# 1_Power_and_sensors.net
KiCad netlist of a schematic drawn in Altium Designer
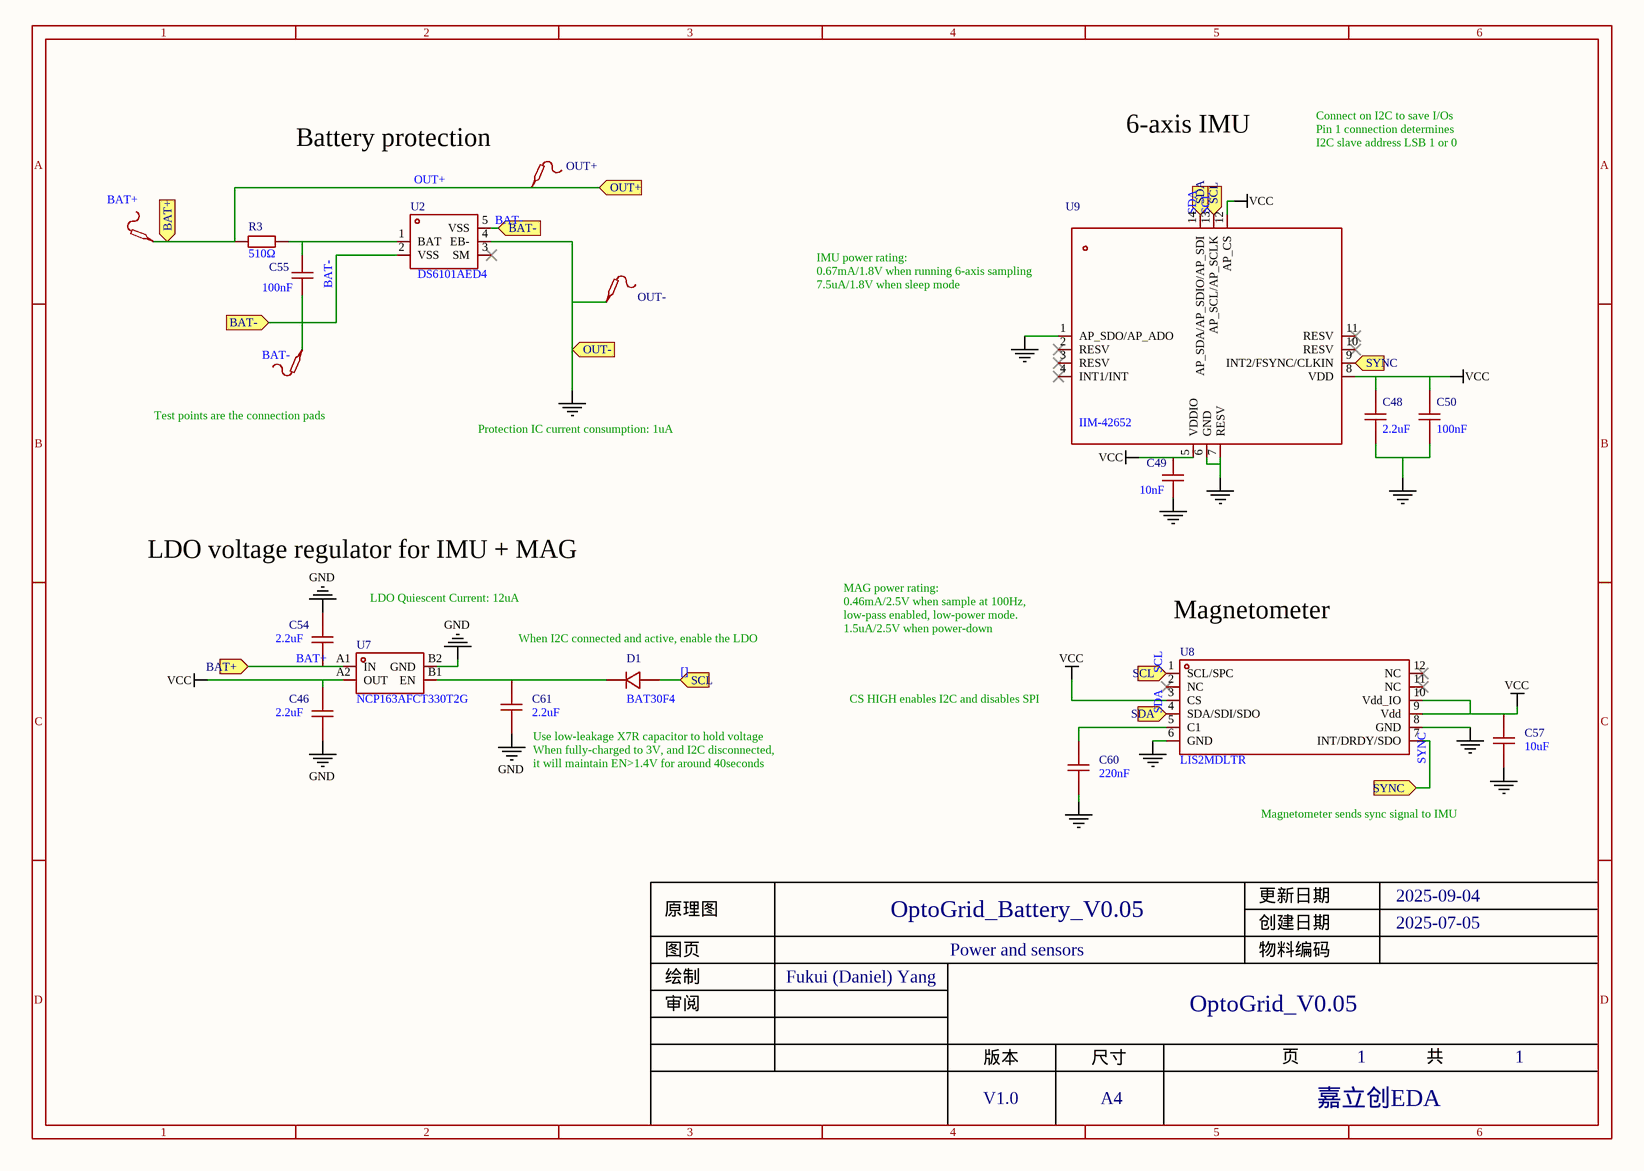
[diagram p0: 1_Power and sensors.schdoc]

(export (version "E")
  (design (tool "Eeschema 10.0.6"))
  (components
    (comp (ref "BAT+")
      (value "~")
      (footprint "Test-Point-0.5mm")
      (libsource (lib "altium-import") (part "root_1_Test-Point_"))
    )
    (comp (ref "BAT-")
      (value "~")
      (footprint "Test-Point-0.5mm")
      (libsource (lib "altium-import") (part "root_2_Test-Point_"))
    )
    (comp (ref "C46")
      (value "2.2uF")
      (footprint "C0201")
      (fields
        (field (name "MANUFACTURER") "muRata(村田)")
        (field (name "MANUFACTURER PART") "GRM033R61A225KE47D")
        (field (name "TOLERANCE") "±10%")
      )
      (libsource (lib "altium-import") (part "root_0_GRM033R61A225KE47D_"))
    )
    (comp (ref "C48")
      (value "2.2uF")
      (footprint "C0201")
      (fields
        (field (name "MANUFACTURER") "muRata(村田)")
        (field (name "MANUFACTURER PART") "GRM033R61A225KE47D")
        (field (name "TOLERANCE") "±10%")
      )
      (libsource (lib "altium-import") (part "root_0_GRM033R61A225KE47D_"))
    )
    (comp (ref "C49")
      (value "10nF")
      (footprint "C0201")
      (fields
        (field (name "MANUFACTURER") "muRata(村田)")
        (field (name "MANUFACTURER PART") "GRM033R71A103KA01D")
        (field (name "TOLERANCE") "±10%")
      )
      (libsource (lib "altium-import") (part "root_1_GRM033R71A103KA01D_"))
    )
    (comp (ref "C50")
      (value "100nF")
      (footprint "C0201")
      (fields
        (field (name "MANUFACTURER") "muRata(村田)")
        (field (name "MANUFACTURER PART") "GRM033Z71A104KE14D")
        (field (name "TOLERANCE") "±10%")
      )
      (libsource (lib "altium-import") (part "root_0_GRM033Z71A104KE14D_"))
    )
    (comp (ref "C54")
      (value "2.2uF")
      (footprint "C0201")
      (fields
        (field (name "MANUFACTURER") "muRata(村田)")
        (field (name "MANUFACTURER PART") "GRM033R61A225KE47D")
        (field (name "TOLERANCE") "±10%")
      )
      (libsource (lib "altium-import") (part "root_0_GRM033R61A225KE47D_"))
    )
    (comp (ref "C55")
      (value "100nF")
      (footprint "C0201")
      (fields
        (field (name "MANUFACTURER") "muRata(村田)")
        (field (name "MANUFACTURER PART") "GRM033R61E104KE14D")
        (field (name "TOLERANCE") "±10%")
      )
      (libsource (lib "altium-import") (part "root_3_GRM033R61E104KE14D_"))
    )
    (comp (ref "C57")
      (value "10uF")
      (footprint "C0402")
      (fields
        (field (name "MANUFACTURER") "SAMSUNG(三星)")
        (field (name "MANUFACTURER PART") "CL05A106MP5NUNC")
        (field (name "TOLERANCE") "±20%")
      )
      (libsource (lib "altium-import") (part "root_1_CL05A106MP5NUNC_"))
    )
    (comp (ref "C60")
      (value "220nF")
      (footprint "C0201")
      (fields
        (field (name "MANUFACTURER") "muRata(村田)")
        (field (name "MANUFACTURER PART") "GRM033R61E224KE01D")
        (field (name "TOLERANCE") "±10%")
      )
      (libsource (lib "altium-import") (part "root_1_GRM033R61E224KE01D_"))
    )
    (comp (ref "C61")
      (value "2.2uF")
      (footprint "C0402")
      (fields
        (field (name "MANUFACTURER") "muRata(村田)")
        (field (name "MANUFACTURER PART") "GRM155Z71A225KE01D")
        (field (name "TOLERANCE") "±10%")
      )
      (libsource (lib "altium-import") (part "root_1_GRM155Z71A225KE01D_"))
    )
    (comp (ref "D1")
      (value "BAT30F4")
      (footprint "DFN0603-D_L0.6-W0.3-P0.34-RD")
      (fields (field (name "MANUFACTURER") "ST(意法半导体)"))
      (libsource (lib "altium-import") (part "root_0_BAT30F4_"))
    )
    (comp (ref "OUT+")
      (value "~")
      (footprint "Test-Point-0.5mm")
      (libsource (lib "altium-import") (part "root_0_Test-Point_"))
    )
    (comp (ref "OUT-")
      (value "~")
      (footprint "Test-Point-0.5mm")
      (libsource (lib "altium-import") (part "root_0_Test-Point_"))
    )
    (comp (ref "R3")
      (value "510Ω")
      (footprint "R0201")
      (fields
        (field (name "MANUFACTURER") "YAGEO(国巨)")
        (field (name "MANUFACTURER PART") "RC0201FR-07510RL")
        (field (name "TOLERANCE") "±1%")
      )
      (libsource (lib "altium-import") (part "root_0_RC0201FR-07510RL_"))
    )
    (comp (ref "U2")
      (value "DS6101AED4")
      (footprint "DFN-4_L1.0-W1.0-P0.65-BL-EP")
      (fields (field (name "MANUFACTURER") "DSTECH(奥简科技)"))
      (libsource (lib "altium-import") (part "root_0_DS6101AED4_"))
    )
    (comp (ref "U7")
      (value "NCP163AFCT330T2G")
      (footprint "WLCSP-4_L0.6-W0.6-P0.35-R2-C2-TL")
      (fields (field (name "MANUFACTURER") "onsemi(安森美)"))
      (libsource (lib "altium-import") (part "root_0_NCP163AFCT330T2G_"))
    )
    (comp (ref "U8")
      (value "LIS2MDLTR")
      (footprint "LGA-12_L2.0-W2.0-P0.50-BL")
      (fields (field (name "MANUFACTURER") "ST(意法半导体)"))
      (libsource (lib "altium-import") (part "root_0_LIS2MDLTR_"))
    )
    (comp (ref "U9")
      (value "IIM-42652")
      (footprint "LGA-14_L3.0-W2.5-P0.50-TL")
      (fields (field (name "MANUFACTURER") "TDK InvenSense(应美盛)"))
      (libsource (lib "altium-import") (part "root_0_IIM-42652_"))
    )
  )
  (nets
    (net (code "1") (name "/BAT+") (class "Default")
      (node (ref "BAT+") (pin "1") (pinfunction "1_1") (pintype "passive"))
      (node (ref "C54") (pin "1") (pinfunction "1_1") (pintype "passive"))
      (node (ref "OUT+") (pin "1") (pinfunction "1_1") (pintype "passive"))
      (node (ref "R3") (pin "1") (pinfunction "1_1") (pintype "passive"))
      (node (ref "U7") (pin "A1") (pinfunction "IN_A1") (pintype "passive"))
    )
    (net (code "2") (name "/BAT-") (class "Default")
      (node (ref "BAT-") (pin "1") (pinfunction "1_1") (pintype "passive"))
      (node (ref "C55") (pin "2") (pinfunction "2_2") (pintype "passive"))
      (node (ref "U2") (pin "2") (pinfunction "VSS_2") (pintype "passive"))
      (node (ref "U2") (pin "5") (pinfunction "VSS_5") (pintype "passive"))
    )
    (net (code "3") (name "/SCL") (class "Default")
      (node (ref "D1") (pin "2") (pinfunction "2_2") (pintype "passive"))
      (node (ref "U8") (pin "1") (pinfunction "SCL/SPC_1") (pintype "passive"))
      (node (ref "U9") (pin "13") (pinfunction "AP_SCL/AP_SCLK_13") (pintype "passive"))
    )
    (net (code "4") (name "/SDA") (class "Default")
      (node (ref "U8") (pin "4") (pinfunction "SDA/SDI/SDO_4") (pintype "passive"))
      (node (ref "U9") (pin "14") (pinfunction "AP_SDA/AP_SDIO/AP_SDI_14") (pintype "passive"))
    )
    (net (code "5") (name "/SYNC") (class "Default")
      (node (ref "U8") (pin "7") (pinfunction "INT/DRDY/SDO_7") (pintype "passive"))
      (node (ref "U9") (pin "9") (pinfunction "INT2/FSYNC/CLKIN_9") (pintype "passive"))
    )
    (net (code "6") (name "GND") (class "Default")
      (node (ref "C46") (pin "1") (pinfunction "1_1") (pintype "passive"))
      (node (ref "C48") (pin "1") (pinfunction "1_1") (pintype "passive"))
      (node (ref "C49") (pin "1") (pinfunction "1_1") (pintype "passive"))
      (node (ref "C50") (pin "1") (pinfunction "1_1") (pintype "passive"))
      (node (ref "C54") (pin "2") (pinfunction "2_2") (pintype "passive"))
      (node (ref "C57") (pin "1") (pinfunction "1_1") (pintype "passive"))
      (node (ref "C60") (pin "1") (pinfunction "1_1") (pintype "passive"))
      (node (ref "C61") (pin "1") (pinfunction "1_1") (pintype "passive"))
      (node (ref "OUT-") (pin "1") (pinfunction "1_1") (pintype "passive"))
      (node (ref "U2") (pin "4") (pinfunction "EB-_4") (pintype "passive"))
      (node (ref "U7") (pin "B2") (pinfunction "GND_B2") (pintype "passive"))
      (node (ref "U8") (pin "6") (pinfunction "GND_6") (pintype "passive"))
      (node (ref "U8") (pin "8") (pinfunction "GND_8") (pintype "passive"))
      (node (ref "U9") (pin "1") (pinfunction "AP_SDO/AP_ADO_1") (pintype "passive"))
      (node (ref "U9") (pin "6") (pinfunction "GND_6") (pintype "passive"))
      (node (ref "U9") (pin "7") (pinfunction "RESV_7") (pintype "passive"))
    )
    (net (code "7") (name "Net-(U2-BAT)") (class "Default")
      (node (ref "C55") (pin "1") (pinfunction "1_1") (pintype "passive"))
      (node (ref "R3") (pin "2") (pinfunction "2_2") (pintype "passive"))
      (node (ref "U2") (pin "1") (pinfunction "BAT_1") (pintype "passive"))
    )
    (net (code "8") (name "Net-(U7-EN)") (class "Default")
      (node (ref "C61") (pin "2") (pinfunction "2_2") (pintype "passive"))
      (node (ref "D1") (pin "1") (pinfunction "1_1") (pintype "passive"))
      (node (ref "U7") (pin "B1") (pinfunction "EN_B1") (pintype "passive"))
    )
    (net (code "9") (name "Net-(U8-C1)") (class "Default")
      (node (ref "C60") (pin "2") (pinfunction "2_2") (pintype "passive"))
      (node (ref "U8") (pin "5") (pinfunction "C1_5") (pintype "passive"))
    )
    (net (code "10") (name "VCC") (class "Default")
      (node (ref "C46") (pin "2") (pinfunction "2_2") (pintype "passive"))
      (node (ref "C48") (pin "2") (pinfunction "2_2") (pintype "passive"))
      (node (ref "C49") (pin "2") (pinfunction "2_2") (pintype "passive"))
      (node (ref "C50") (pin "2") (pinfunction "2_2") (pintype "passive"))
      (node (ref "C57") (pin "2") (pinfunction "2_2") (pintype "passive"))
      (node (ref "U7") (pin "A2") (pinfunction "OUT_A2") (pintype "passive"))
      (node (ref "U8") (pin "10") (pinfunction "Vdd_IO_10") (pintype "passive"))
      (node (ref "U8") (pin "3") (pinfunction "CS_3") (pintype "passive"))
      (node (ref "U8") (pin "9") (pinfunction "Vdd_9") (pintype "passive"))
      (node (ref "U9") (pin "12") (pinfunction "AP_CS_12") (pintype "passive"))
      (node (ref "U9") (pin "5") (pinfunction "VDDIO_5") (pintype "passive"))
      (node (ref "U9") (pin "8") (pinfunction "VDD_8") (pintype "passive"))
    )
    (net (code "11") (name "unconnected-(U2-SM-Pad3)") (class "Default")
      (node (ref "U2") (pin "3") (pinfunction "SM_3") (pintype "passive+no_connect"))
    )
    (net (code "12") (name "unconnected-(U8-NC-Pad2)") (class "Default")
      (node (ref "U8") (pin "2") (pinfunction "NC_2") (pintype "passive+no_connect"))
    )
    (net (code "13") (name "unconnected-(U8-NC-Pad11)") (class "Default")
      (node (ref "U8") (pin "11") (pinfunction "NC_11") (pintype "passive+no_connect"))
    )
    (net (code "14") (name "unconnected-(U8-NC-Pad12)") (class "Default")
      (node (ref "U8") (pin "12") (pinfunction "NC_12") (pintype "passive+no_connect"))
    )
    (net (code "15") (name "unconnected-(U9-INT1{slash}INT-Pad4)") (class "Default")
      (node (ref "U9") (pin "4") (pinfunction "INT1/INT_4") (pintype "passive+no_connect"))
    )
    (net (code "16") (name "unconnected-(U9-RESV-Pad2)") (class "Default")
      (node (ref "U9") (pin "2") (pinfunction "RESV_2") (pintype "passive+no_connect"))
    )
    (net (code "17") (name "unconnected-(U9-RESV-Pad3)") (class "Default")
      (node (ref "U9") (pin "3") (pinfunction "RESV_3") (pintype "passive+no_connect"))
    )
    (net (code "18") (name "unconnected-(U9-RESV-Pad10)") (class "Default")
      (node (ref "U9") (pin "10") (pinfunction "RESV_10") (pintype "passive+no_connect"))
    )
    (net (code "19") (name "unconnected-(U9-RESV-Pad11)") (class "Default")
      (node (ref "U9") (pin "11") (pinfunction "RESV_11") (pintype "passive+no_connect"))
    )
  )
)
